# USB_TTL.net
KiCad netlist of a schematic drawn in Altium Designer
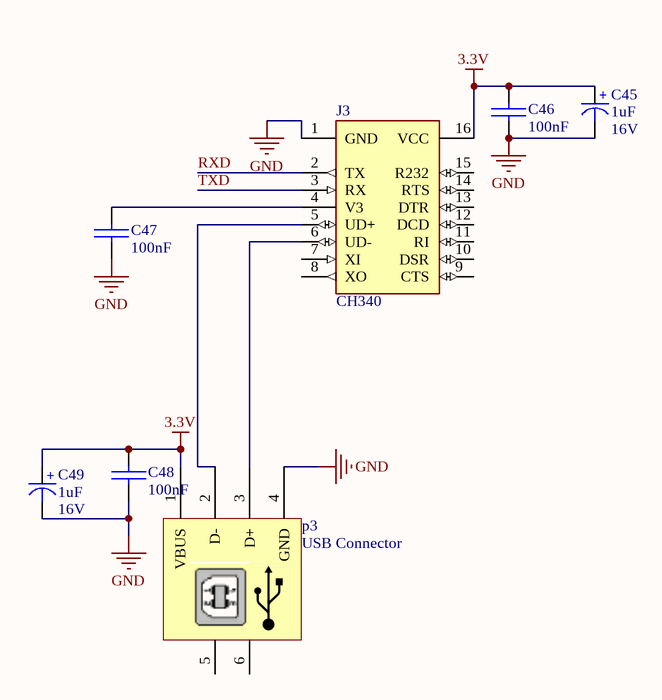
[diagram p0: USB_TTL.SchDoc]

(export (version "E")
  (design (tool "Eeschema 10.0.6"))
  (components
    (comp (ref "C45")
      (value "1uF")
      (footprint "cap 01")
      (description "Polar Capacitor")
      (fields (field (name "VOLTAGE") "16V") (field (name "DESIGNER") "Saeid Jorablo"))
      (libsource (lib "My Library") (part "Cap-Polar"))
    )
    (comp (ref "C46")
      (value "100nF")
      (footprint "SMD_CAP_1206")
      (description "Bipolar Capacitor")
      (fields (field (name "VOLTAGE") "100V") (field (name "DESIGNER") "Saeid Jorablo"))
      (libsource (lib "My Library") (part "Cap-Bipolar"))
    )
    (comp (ref "C47")
      (value "100nF")
      (footprint "SMD_CAP_1206")
      (description "Bipolar Capacitor")
      (fields (field (name "VOLTAGE") "100V") (field (name "DESIGNER") "Saeid Jorablo"))
      (libsource (lib "My Library") (part "Cap-Bipolar"))
    )
    (comp (ref "C48")
      (value "100nF")
      (footprint "SMD_CAP_1206")
      (description "Bipolar Capacitor")
      (fields (field (name "VOLTAGE") "100V") (field (name "DESIGNER") "Saeid Jorablo"))
      (libsource (lib "My Library") (part "Cap-Bipolar"))
    )
    (comp (ref "C49")
      (value "1uF")
      (footprint "cap 01")
      (description "Polar Capacitor")
      (fields (field (name "VOLTAGE") "16V") (field (name "DESIGNER") "Saeid Jorablo"))
      (libsource (lib "My Library") (part "Cap-Polar"))
    )
    (comp (ref "J3")
      (value "CH340")
      (footprint "SOIC16")
      (description "CH340G USB 2.0 to UART (RS232/RS422/RS485) Bridge Interface Evaluation Board")
      (fields (field (name "MF") "DFRobot"))
      (libsource (lib "CH340") (part "CH340"))
    )
    (comp (ref "p3")
      (value "USB Connector")
      (footprint "USB2.5-2H4F")
      (description "USB Connector-B Type")
      (fields (field (name "DESIGNER") "Eng. Saeid Jorablo"))
      (libsource (lib "My Library") (part "USB"))
    )
  )
  (nets
    (net (code "1") (name "/RXD") (class "Default")
      (node (ref "J3") (pin "2") (pinfunction "TX_2") (pintype "output"))
    )
    (net (code "2") (name "/TXD") (class "Default")
      (node (ref "J3") (pin "3") (pinfunction "RX_3") (pintype "input"))
    )
    (net (code "3") (name "3.3V") (class "Default")
      (node (ref "C45") (pin "1") (pinfunction "+_1") (pintype "passive"))
      (node (ref "C46") (pin "1") (pinfunction "+_1") (pintype "passive"))
      (node (ref "C48") (pin "1") (pinfunction "+_1") (pintype "passive"))
      (node (ref "C49") (pin "1") (pinfunction "+_1") (pintype "passive"))
      (node (ref "J3") (pin "16") (pinfunction "VCC_16") (pintype "power_in"))
      (node (ref "p3") (pin "1") (pinfunction "VBUS_1") (pintype "power_in"))
    )
    (net (code "4") (name "GND") (class "Default")
      (node (ref "C45") (pin "2") (pinfunction "-_2") (pintype "passive"))
      (node (ref "C46") (pin "2") (pinfunction "-_2") (pintype "passive"))
      (node (ref "C47") (pin "2") (pinfunction "-_2") (pintype "passive"))
      (node (ref "C48") (pin "2") (pinfunction "-_2") (pintype "passive"))
      (node (ref "C49") (pin "2") (pinfunction "-_2") (pintype "passive"))
      (node (ref "J3") (pin "1") (pinfunction "GND_1") (pintype "power_in"))
      (node (ref "p3") (pin "4") (pinfunction "GND_4") (pintype "power_in"))
    )
    (net (code "5") (name "Net-(C47-+)") (class "Default")
      (node (ref "C47") (pin "1") (pinfunction "+_1") (pintype "passive"))
      (node (ref "J3") (pin "4") (pinfunction "V3_4") (pintype "power_in"))
    )
    (net (code "6") (name "Net-(J3-UD+)") (class "Default")
      (node (ref "J3") (pin "5") (pinfunction "UD+_5") (pintype "bidirectional"))
      (node (ref "p3") (pin "2") (pinfunction "D-_2") (pintype "passive"))
    )
    (net (code "7") (name "Net-(J3-UD-)") (class "Default")
      (node (ref "J3") (pin "6") (pinfunction "UD-_6") (pintype "bidirectional"))
      (node (ref "p3") (pin "3") (pinfunction "D+_3") (pintype "passive"))
    )
    (net (code "8") (name "unconnected-(J3-CTS-Pad9)") (class "Default")
      (node (ref "J3") (pin "9") (pinfunction "CTS_9") (pintype "bidirectional"))
    )
    (net (code "9") (name "unconnected-(J3-DCD-Pad12)") (class "Default")
      (node (ref "J3") (pin "12") (pinfunction "DCD_12") (pintype "bidirectional"))
    )
    (net (code "10") (name "unconnected-(J3-DSR-Pad10)") (class "Default")
      (node (ref "J3") (pin "10") (pinfunction "DSR_10") (pintype "bidirectional"))
    )
    (net (code "11") (name "unconnected-(J3-DTR-Pad13)") (class "Default")
      (node (ref "J3") (pin "13") (pinfunction "DTR_13") (pintype "bidirectional"))
    )
    (net (code "12") (name "unconnected-(J3-R232-Pad15)") (class "Default")
      (node (ref "J3") (pin "15") (pinfunction "R232_15") (pintype "bidirectional"))
    )
    (net (code "13") (name "unconnected-(J3-RI-Pad11)") (class "Default")
      (node (ref "J3") (pin "11") (pinfunction "RI_11") (pintype "bidirectional"))
    )
    (net (code "14") (name "unconnected-(J3-RTS-Pad14)") (class "Default")
      (node (ref "J3") (pin "14") (pinfunction "RTS_14") (pintype "bidirectional"))
    )
    (net (code "15") (name "unconnected-(J3-XI-Pad7)") (class "Default")
      (node (ref "J3") (pin "7") (pinfunction "XI_7") (pintype "input"))
    )
    (net (code "16") (name "unconnected-(J3-XO-Pad8)") (class "Default")
      (node (ref "J3") (pin "8") (pinfunction "XO_8") (pintype "output"))
    )
    (net (code "17") (name "unconnected-(p3-Pad5)") (class "Default")
      (node (ref "p3") (pin "5") (pinfunction "5_5") (pintype "passive"))
    )
    (net (code "18") (name "unconnected-(p3-Pad6)") (class "Default")
      (node (ref "p3") (pin "6") (pinfunction "6_6") (pintype "passive"))
    )
  )
)
